# schematic.net
KiCad netlist of a schematic drawn in EAGLE
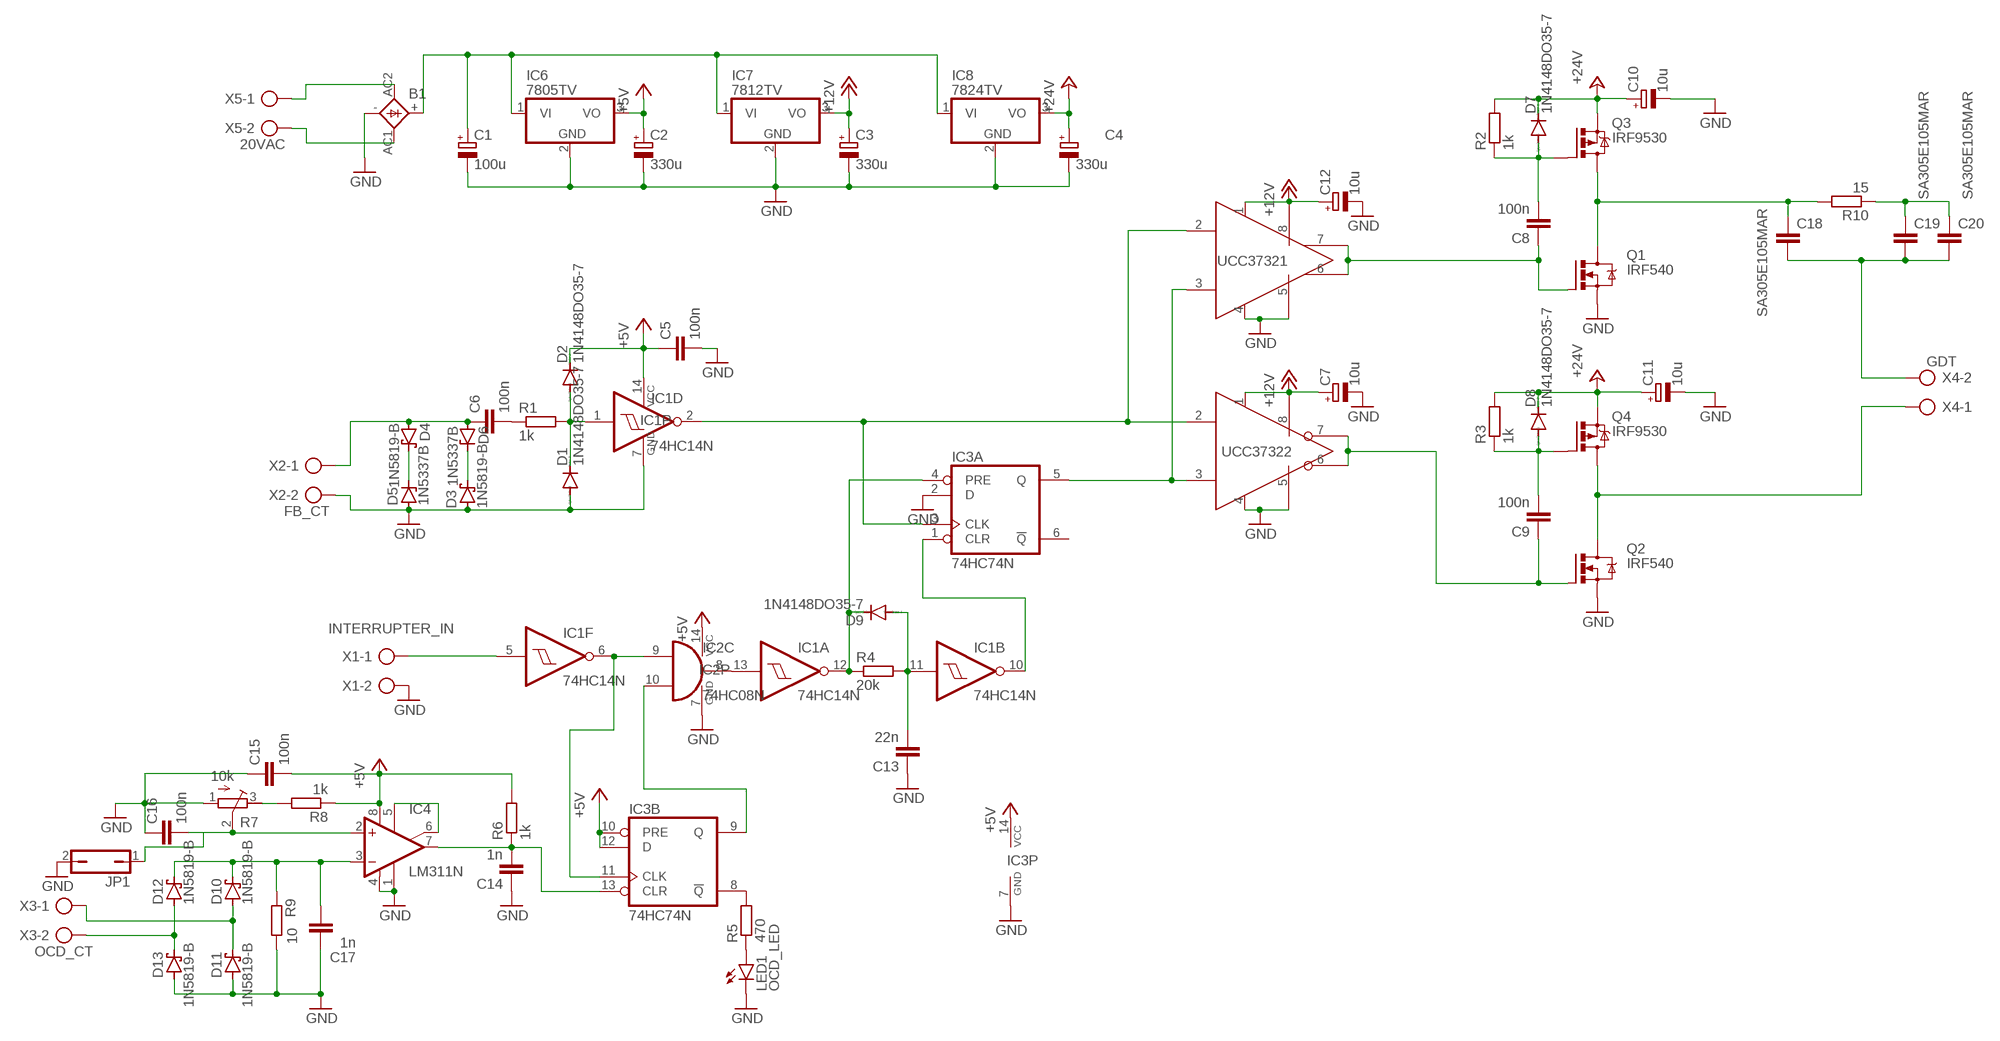
[diagram p0: schematic, sheet 1]

(export (version "E")
  (design (tool "Eeschema 10.0.6"))
  (components
    (comp (ref "B1")
      (value "KBL")
      (footprint "eagle-import:KBL")
      (libsource (lib "eagle-import") (part "KBL"))
    )
    (comp (ref "C1")
      (value "100u")
      (footprint "eagle-import:E3,5-10")
      (libsource (lib "eagle-import") (part "CPOL-EUE3.5-10"))
    )
    (comp (ref "C2")
      (value "330u")
      (footprint "eagle-import:E3,5-10")
      (libsource (lib "eagle-import") (part "CPOL-EUE3.5-10"))
    )
    (comp (ref "C3")
      (value "330u")
      (footprint "eagle-import:E3,5-10")
      (libsource (lib "eagle-import") (part "CPOL-EUE3.5-10"))
    )
    (comp (ref "C4")
      (value "330u")
      (footprint "eagle-import:E3,5-10")
      (libsource (lib "eagle-import") (part "CPOL-EUE3.5-10"))
    )
    (comp (ref "C5")
      (value "100n")
      (footprint "eagle-import:C050-030X075")
      (libsource (lib "eagle-import") (part "C-EU050-030X075"))
    )
    (comp (ref "C6")
      (value "100n")
      (footprint "eagle-import:C050-030X075")
      (libsource (lib "eagle-import") (part "C-EU050-030X075"))
    )
    (comp (ref "C7")
      (value "10u")
      (footprint "eagle-import:E2,5-6")
      (libsource (lib "eagle-import") (part "CPOL-EUE2.5-6"))
    )
    (comp (ref "C8")
      (value "100n")
      (footprint "eagle-import:C050-030X075")
      (libsource (lib "eagle-import") (part "C-EU050-030X075"))
    )
    (comp (ref "C9")
      (value "100n")
      (footprint "eagle-import:C050-030X075")
      (libsource (lib "eagle-import") (part "C-EU050-030X075"))
    )
    (comp (ref "C10")
      (value "10u")
      (footprint "eagle-import:E2,5-6")
      (libsource (lib "eagle-import") (part "CPOL-EUE2.5-6"))
    )
    (comp (ref "C11")
      (value "10u")
      (footprint "eagle-import:E2,5-6")
      (libsource (lib "eagle-import") (part "CPOL-EUE2.5-6"))
    )
    (comp (ref "C12")
      (value "10u")
      (footprint "eagle-import:E2,5-6")
      (libsource (lib "eagle-import") (part "CPOL-EUE2.5-6"))
    )
    (comp (ref "C13")
      (value "22n")
      (footprint "eagle-import:C050-030X075")
      (libsource (lib "eagle-import") (part "C-EU050-030X075"))
    )
    (comp (ref "C14")
      (value "1n")
      (footprint "eagle-import:C050-030X075")
      (libsource (lib "eagle-import") (part "C-EU050-030X075"))
    )
    (comp (ref "C15")
      (value "100n")
      (footprint "eagle-import:C050-030X075")
      (libsource (lib "eagle-import") (part "C-EU050-030X075"))
    )
    (comp (ref "C16")
      (value "100n")
      (footprint "eagle-import:C050-030X075")
      (libsource (lib "eagle-import") (part "C-EU050-030X075"))
    )
    (comp (ref "C17")
      (value "1n")
      (footprint "eagle-import:C050-030X075")
      (libsource (lib "eagle-import") (part "C-EU050-030X075"))
    )
    (comp (ref "C18")
      (value "SA305E105MAR")
      (footprint "eagle-import:C050-025X075")
      (libsource (lib "eagle-import") (part "resistor_348_C-EU050-025X075"))
    )
    (comp (ref "C19")
      (value "SA305E105MAR")
      (footprint "eagle-import:C050-025X075")
      (libsource (lib "eagle-import") (part "resistor_348_C-EU050-025X075"))
    )
    (comp (ref "C20")
      (value "SA305E105MAR")
      (footprint "eagle-import:C050-025X075")
      (libsource (lib "eagle-import") (part "resistor_348_C-EU050-025X075"))
    )
    (comp (ref "D1")
      (value "1N4148DO35-7")
      (footprint "eagle-import:DO35-7")
      (libsource (lib "eagle-import") (part "1N4148DO35-7"))
    )
    (comp (ref "D2")
      (value "1N4148DO35-7")
      (footprint "eagle-import:DO35-7")
      (libsource (lib "eagle-import") (part "1N4148DO35-7"))
    )
    (comp (ref "D3")
      (value "1N5819-B")
      (footprint "eagle-import:DO41-7.6")
      (libsource (lib "eagle-import") (part "1N5819-B"))
    )
    (comp (ref "D4")
      (value "1N5819-B")
      (footprint "eagle-import:DO41-7.6")
      (libsource (lib "eagle-import") (part "1N5819-B"))
    )
    (comp (ref "D5")
      (value "1N5337B")
      (footprint "eagle-import:DO41Z10")
      (libsource (lib "eagle-import") (part "ZENER-DIODEDO41Z10"))
    )
    (comp (ref "D6")
      (value "1N5337B")
      (footprint "eagle-import:DO41Z10")
      (libsource (lib "eagle-import") (part "ZENER-DIODEDO41Z10"))
    )
    (comp (ref "D7")
      (value "1N4148DO35-7")
      (footprint "eagle-import:DO35-7")
      (libsource (lib "eagle-import") (part "1N4148DO35-7"))
    )
    (comp (ref "D8")
      (value "1N4148DO35-7")
      (footprint "eagle-import:DO35-7")
      (libsource (lib "eagle-import") (part "1N4148DO35-7"))
    )
    (comp (ref "D9")
      (value "1N4148DO35-7")
      (footprint "eagle-import:DO35-7")
      (libsource (lib "eagle-import") (part "1N4148DO35-7"))
    )
    (comp (ref "D10")
      (value "1N5819-B")
      (footprint "eagle-import:DO41-7.6")
      (libsource (lib "eagle-import") (part "1N5819-B"))
    )
    (comp (ref "D11")
      (value "1N5819-B")
      (footprint "eagle-import:DO41-7.6")
      (libsource (lib "eagle-import") (part "1N5819-B"))
    )
    (comp (ref "D12")
      (value "1N5819-B")
      (footprint "eagle-import:DO41-7.6")
      (libsource (lib "eagle-import") (part "1N5819-B"))
    )
    (comp (ref "D13")
      (value "1N5819-B")
      (footprint "eagle-import:DO41-7.6")
      (libsource (lib "eagle-import") (part "1N5819-B"))
    )
    (comp (ref "IC1")
      (value "74HC14N")
      (footprint "eagle-import:DIL14")
      (libsource (lib "eagle-import") (part "7414NHC"))
    )
    (comp (ref "IC2")
      (value "74HC08N")
      (footprint "eagle-import:DIL14")
      (libsource (lib "eagle-import") (part "7408NHC"))
    )
    (comp (ref "IC3")
      (value "74HC74N")
      (footprint "eagle-import:DIL14")
      (libsource (lib "eagle-import") (part "7474NHC"))
    )
    (comp (ref "IC4")
      (value "LM311N")
      (footprint "eagle-import:DIL08")
      (libsource (lib "eagle-import") (part "LM311N"))
    )
    (comp (ref "IC5")
      (value "UCC37321DIL8")
      (footprint "eagle-import:DIL08")
      (fields (field (name "MF") "Texas Instruments") (field (name "MP") "UCC37321"))
      (libsource (lib "eagle-import") (part "UCC37321DIL8"))
    )
    (comp (ref "IC6")
      (value "7805TV")
      (footprint "eagle-import:TO220V")
      (libsource (lib "eagle-import") (part "78TV05"))
    )
    (comp (ref "IC7")
      (value "7812TV")
      (footprint "eagle-import:TO220V")
      (libsource (lib "eagle-import") (part "78TV12"))
    )
    (comp (ref "IC8")
      (value "7824TV")
      (footprint "eagle-import:TO220V")
      (libsource (lib "eagle-import") (part "78TV24"))
    )
    (comp (ref "IC9")
      (value "UCC37322DIL8")
      (footprint "eagle-import:DIL08")
      (fields (field (name "MF") "Texas Instruments") (field (name "MP") "UCC37322"))
      (libsource (lib "eagle-import") (part "UCC37322DIL8"))
    )
    (comp (ref "JP1")
      (value "JP1Q")
      (footprint "eagle-import:JP1")
      (libsource (lib "eagle-import") (part "JP1Q"))
    )
    (comp (ref "LED1")
      (value "OCD_LED")
      (footprint "eagle-import:LED3MM")
      (libsource (lib "eagle-import") (part "LED3MM"))
    )
    (comp (ref "Q1")
      (value "IRF540")
      (footprint "eagle-import:TO220BV")
      (libsource (lib "eagle-import") (part "IRF540"))
    )
    (comp (ref "Q2")
      (value "IRF540")
      (footprint "eagle-import:TO220BV")
      (libsource (lib "eagle-import") (part "IRF540"))
    )
    (comp (ref "Q3")
      (value "IRF9530")
      (footprint "eagle-import:TO220BV")
      (libsource (lib "eagle-import") (part "IRF9530"))
    )
    (comp (ref "Q4")
      (value "IRF9530")
      (footprint "eagle-import:TO220BV")
      (libsource (lib "eagle-import") (part "IRF9530"))
    )
    (comp (ref "R1")
      (value "1k")
      (footprint "eagle-import:0204_7")
      (libsource (lib "eagle-import") (part "R-EU_0204/7"))
    )
    (comp (ref "R2")
      (value "1k")
      (footprint "eagle-import:0204_7")
      (libsource (lib "eagle-import") (part "R-EU_0204/7"))
    )
    (comp (ref "R3")
      (value "1k")
      (footprint "eagle-import:0204_7")
      (libsource (lib "eagle-import") (part "R-EU_0204/7"))
    )
    (comp (ref "R4")
      (value "20k")
      (footprint "eagle-import:0204_7")
      (libsource (lib "eagle-import") (part "R-EU_0204/7"))
    )
    (comp (ref "R5")
      (value "470")
      (footprint "eagle-import:0204_7")
      (libsource (lib "eagle-import") (part "R-EU_0204/7"))
    )
    (comp (ref "R6")
      (value "1k")
      (footprint "eagle-import:0204_7")
      (libsource (lib "eagle-import") (part "R-EU_0204/7"))
    )
    (comp (ref "R7")
      (value "10k")
      (footprint "eagle-import:RTRIM64X")
      (libsource (lib "eagle-import") (part "R-TRIMM64X"))
    )
    (comp (ref "R8")
      (value "1k")
      (footprint "eagle-import:0204_7")
      (libsource (lib "eagle-import") (part "R-EU_0204/7"))
    )
    (comp (ref "R9")
      (value "10")
      (footprint "eagle-import:0411_15")
      (libsource (lib "eagle-import") (part "R-EU_0411/15"))
    )
    (comp (ref "R10")
      (value "15")
      (footprint "eagle-import:0204_7")
      (libsource (lib "eagle-import") (part "R-EU_0204/7"))
    )
    (comp (ref "X1")
      (value "INTERRUPTER_IN")
      (footprint "eagle-import:AK300_2")
      (libsource (lib "eagle-import") (part "AK300/2"))
    )
    (comp (ref "X2")
      (value "FB_CT")
      (footprint "eagle-import:AK300_2")
      (libsource (lib "eagle-import") (part "AK300/2"))
    )
    (comp (ref "X3")
      (value "OCD_CT")
      (footprint "eagle-import:AK300_2")
      (libsource (lib "eagle-import") (part "AK300/2"))
    )
    (comp (ref "X4")
      (value "GDT")
      (footprint "eagle-import:AK300_2")
      (libsource (lib "eagle-import") (part "AK300/2"))
    )
    (comp (ref "X5")
      (value "20VAC")
      (footprint "eagle-import:AK300_2")
      (libsource (lib "eagle-import") (part "AK300/2"))
    )
  )
  (nets
    (net (code "1") (name "+5V") (class "Default")
      (node (ref "C15") (pin "2") (pinfunction "2_2") (pintype "passive"))
      (node (ref "C2") (pin "+") (pinfunction "+_+") (pintype "passive"))
      (node (ref "C5") (pin "1") (pinfunction "1_1") (pintype "passive"))
      (node (ref "D2") (pin "C") (pinfunction "C_C") (pintype "passive"))
      (node (ref "IC1") (pin "14") (pinfunction "VCC_14") (pintype "power_in"))
      (node (ref "IC2") (pin "14") (pinfunction "VCC_14") (pintype "power_in"))
      (node (ref "IC3") (pin "10") (pinfunction "PRE_10") (pintype "input"))
      (node (ref "IC3") (pin "12") (pinfunction "D_12") (pintype "input"))
      (node (ref "IC3") (pin "14") (pinfunction "VCC_14") (pintype "power_in"))
      (node (ref "IC4") (pin "8") (pinfunction "V+_8") (pintype "power_in"))
      (node (ref "IC6") (pin "3") (pinfunction "VO_3") (pintype "passive"))
      (node (ref "R6") (pin "2") (pinfunction "2_2") (pintype "passive"))
      (node (ref "R8") (pin "1") (pinfunction "1_1") (pintype "passive"))
    )
    (net (code "2") (name "+12V") (class "Default")
      (node (ref "C12") (pin "+") (pinfunction "+_+") (pintype "passive"))
      (node (ref "C3") (pin "+") (pinfunction "+_+") (pintype "passive"))
      (node (ref "C7") (pin "+") (pinfunction "+_+") (pintype "passive"))
      (node (ref "IC5") (pin "1") (pinfunction "1_VDD_1") (pintype "power_in"))
      (node (ref "IC5") (pin "8") (pinfunction "8_VDD_8") (pintype "power_in"))
      (node (ref "IC7") (pin "3") (pinfunction "VO_3") (pintype "passive"))
      (node (ref "IC9") (pin "1") (pinfunction "1_VDD_1") (pintype "power_in"))
      (node (ref "IC9") (pin "8") (pinfunction "8_VDD_8") (pintype "power_in"))
    )
    (net (code "3") (name "+24V") (class "Default")
      (node (ref "C10") (pin "+") (pinfunction "+_+") (pintype "passive"))
      (node (ref "C11") (pin "+") (pinfunction "+_+") (pintype "passive"))
      (node (ref "C4") (pin "+") (pinfunction "+_+") (pintype "passive"))
      (node (ref "D7") (pin "C") (pinfunction "C_C") (pintype "passive"))
      (node (ref "D8") (pin "C") (pinfunction "C_C") (pintype "passive"))
      (node (ref "IC8") (pin "3") (pinfunction "VO_3") (pintype "passive"))
      (node (ref "Q3") (pin "S") (pinfunction "S_S") (pintype "passive"))
      (node (ref "Q4") (pin "S") (pinfunction "S_S") (pintype "passive"))
      (node (ref "R2") (pin "2") (pinfunction "2_2") (pintype "passive"))
      (node (ref "R3") (pin "2") (pinfunction "2_2") (pintype "passive"))
    )
    (net (code "4") (name "GND") (class "Default")
      (node (ref "B1") (pin "-") (pinfunction "-_-") (pintype "passive"))
      (node (ref "C1") (pin "-") (pinfunction "-_-") (pintype "passive"))
      (node (ref "C10") (pin "-") (pinfunction "-_-") (pintype "passive"))
      (node (ref "C11") (pin "-") (pinfunction "-_-") (pintype "passive"))
      (node (ref "C12") (pin "-") (pinfunction "-_-") (pintype "passive"))
      (node (ref "C13") (pin "1") (pinfunction "1_1") (pintype "passive"))
      (node (ref "C14") (pin "1") (pinfunction "1_1") (pintype "passive"))
      (node (ref "C15") (pin "1") (pinfunction "1_1") (pintype "passive"))
      (node (ref "C16") (pin "1") (pinfunction "1_1") (pintype "passive"))
      (node (ref "C17") (pin "1") (pinfunction "1_1") (pintype "passive"))
      (node (ref "C2") (pin "-") (pinfunction "-_-") (pintype "passive"))
      (node (ref "C3") (pin "-") (pinfunction "-_-") (pintype "passive"))
      (node (ref "C4") (pin "-") (pinfunction "-_-") (pintype "passive"))
      (node (ref "C5") (pin "2") (pinfunction "2_2") (pintype "passive"))
      (node (ref "C7") (pin "-") (pinfunction "-_-") (pintype "passive"))
      (node (ref "D1") (pin "A") (pinfunction "A_A") (pintype "passive"))
      (node (ref "D11") (pin "A") (pinfunction "A_A") (pintype "passive"))
      (node (ref "D13") (pin "A") (pinfunction "A_A") (pintype "passive"))
      (node (ref "D3") (pin "A") (pinfunction "A_A") (pintype "passive"))
      (node (ref "D5") (pin "A") (pinfunction "A_A") (pintype "passive"))
      (node (ref "IC1") (pin "7") (pinfunction "GND_7") (pintype "power_in"))
      (node (ref "IC2") (pin "7") (pinfunction "GND_7") (pintype "power_in"))
      (node (ref "IC3") (pin "2") (pinfunction "D_2") (pintype "input"))
      (node (ref "IC3") (pin "7") (pinfunction "GND_7") (pintype "power_in"))
      (node (ref "IC4") (pin "1") (pinfunction "GND_1") (pintype "passive"))
      (node (ref "IC4") (pin "4") (pinfunction "V-_4") (pintype "power_in"))
      (node (ref "IC5") (pin "4") (pinfunction "4_AGND_4") (pintype "power_in"))
      (node (ref "IC5") (pin "5") (pinfunction "5_PGND_5") (pintype "power_in"))
      (node (ref "IC6") (pin "2") (pinfunction "GND_2") (pintype "passive"))
      (node (ref "IC7") (pin "2") (pinfunction "GND_2") (pintype "passive"))
      (node (ref "IC8") (pin "2") (pinfunction "GND_2") (pintype "passive"))
      (node (ref "IC9") (pin "4") (pinfunction "4_AGND_4") (pintype "power_in"))
      (node (ref "IC9") (pin "5") (pinfunction "5_PGND_5") (pintype "power_in"))
      (node (ref "JP1") (pin "2") (pinfunction "2_2") (pintype "passive"))
      (node (ref "LED1") (pin "K") (pinfunction "C_K") (pintype "passive"))
      (node (ref "Q1") (pin "S") (pinfunction "S_S") (pintype "passive"))
      (node (ref "Q2") (pin "S") (pinfunction "S_S") (pintype "passive"))
      (node (ref "R7") (pin "1") (pinfunction "A_1") (pintype "passive"))
      (node (ref "R9") (pin "2") (pinfunction "2_2") (pintype "passive"))
      (node (ref "X1") (pin "2") (pinfunction "KL_2") (pintype "passive"))
      (node (ref "X2") (pin "2") (pinfunction "KL_2") (pintype "passive"))
    )
    (net (code "5") (name "Net-(B1-AC1)") (class "Default")
      (node (ref "B1") (pin "AC2") (pinfunction "AC1_AC2") (pintype "passive"))
      (node (ref "X5") (pin "1") (pinfunction "KL_1") (pintype "passive"))
    )
    (net (code "6") (name "Net-(B1-AC2)") (class "Default")
      (node (ref "B1") (pin "AC1") (pinfunction "AC2_AC1") (pintype "passive"))
      (node (ref "X5") (pin "2") (pinfunction "KL_2") (pintype "passive"))
    )
    (net (code "7") (name "Net-(C6-Pad2)") (class "Default")
      (node (ref "C6") (pin "2") (pinfunction "2_2") (pintype "passive"))
      (node (ref "R1") (pin "1") (pinfunction "1_1") (pintype "passive"))
    )
    (net (code "8") (name "Net-(C8-Pad2)") (class "Default")
      (node (ref "C8") (pin "2") (pinfunction "2_2") (pintype "passive"))
      (node (ref "D7") (pin "A") (pinfunction "A_A") (pintype "passive"))
      (node (ref "Q3") (pin "G") (pinfunction "G_G") (pintype "passive"))
      (node (ref "R2") (pin "1") (pinfunction "1_1") (pintype "passive"))
    )
    (net (code "9") (name "Net-(C9-Pad2)") (class "Default")
      (node (ref "C9") (pin "2") (pinfunction "2_2") (pintype "passive"))
      (node (ref "D8") (pin "A") (pinfunction "A_A") (pintype "passive"))
      (node (ref "Q4") (pin "G") (pinfunction "G_G") (pintype "passive"))
      (node (ref "R3") (pin "1") (pinfunction "1_1") (pintype "passive"))
    )
    (net (code "10") (name "Net-(C18-Pad1)") (class "Default")
      (node (ref "C18") (pin "1") (pinfunction "1_1") (pintype "passive"))
      (node (ref "Q1") (pin "D") (pinfunction "D_D") (pintype "passive"))
      (node (ref "Q3") (pin "D") (pinfunction "D_D") (pintype "passive"))
      (node (ref "R10") (pin "2") (pinfunction "2_2") (pintype "passive"))
    )
    (net (code "11") (name "Net-(C19-Pad1)") (class "Default")
      (node (ref "C19") (pin "1") (pinfunction "1_1") (pintype "passive"))
      (node (ref "C20") (pin "1") (pinfunction "1_1") (pintype "passive"))
      (node (ref "R10") (pin "1") (pinfunction "1_1") (pintype "passive"))
    )
    (net (code "12") (name "Net-(D3-PadC)") (class "Default")
      (node (ref "D3") (pin "C") (pinfunction "C_C") (pintype "passive"))
      (node (ref "D6") (pin "C") (pinfunction "C_C") (pintype "passive"))
    )
    (net (code "13") (name "Net-(D4-PadC)") (class "Default")
      (node (ref "D4") (pin "C") (pinfunction "C_C") (pintype "passive"))
      (node (ref "D5") (pin "C") (pinfunction "C_C") (pintype "passive"))
    )
    (net (code "14") (name "Net-(IC1A-I)") (class "Default")
      (node (ref "IC1") (pin "13") (pinfunction "I_13") (pintype "input"))
      (node (ref "IC2") (pin "8") (pinfunction "O_8") (pintype "output"))
    )
    (net (code "15") (name "Net-(IC1A-O)") (class "Default")
      (node (ref "D9") (pin "C") (pinfunction "C_C") (pintype "passive"))
      (node (ref "IC1") (pin "12") (pinfunction "O_12") (pintype "output"))
      (node (ref "IC3") (pin "4") (pinfunction "PRE_4") (pintype "input"))
      (node (ref "R4") (pin "1") (pinfunction "1_1") (pintype "passive"))
    )
    (net (code "16") (name "Net-(IC1B-I)") (class "Default")
      (node (ref "C13") (pin "2") (pinfunction "2_2") (pintype "passive"))
      (node (ref "D9") (pin "A") (pinfunction "A_A") (pintype "passive"))
      (node (ref "IC1") (pin "11") (pinfunction "I_11") (pintype "input"))
      (node (ref "R4") (pin "2") (pinfunction "2_2") (pintype "passive"))
    )
    (net (code "17") (name "Net-(IC1B-O)") (class "Default")
      (node (ref "IC1") (pin "10") (pinfunction "O_10") (pintype "output"))
      (node (ref "IC3") (pin "1") (pinfunction "CLR_1") (pintype "input"))
    )
    (net (code "18") (name "Net-(IC1D-I)") (class "Default")
      (node (ref "D1") (pin "C") (pinfunction "C_C") (pintype "passive"))
      (node (ref "D2") (pin "A") (pinfunction "A_A") (pintype "passive"))
      (node (ref "IC1") (pin "1") (pinfunction "I_1") (pintype "input"))
      (node (ref "R1") (pin "2") (pinfunction "2_2") (pintype "passive"))
    )
    (net (code "19") (name "Net-(IC1D-O)") (class "Default")
      (node (ref "IC1") (pin "2") (pinfunction "O_2") (pintype "output"))
      (node (ref "IC3") (pin "3") (pinfunction "CLK_3") (pintype "input"))
      (node (ref "IC5") (pin "2") (pinfunction "2_IN_2") (pintype "input"))
      (node (ref "IC9") (pin "2") (pinfunction "2_IN_2") (pintype "input"))
    )
    (net (code "20") (name "Net-(IC1F-I)") (class "Default")
      (node (ref "IC1") (pin "5") (pinfunction "I_5") (pintype "input"))
      (node (ref "X1") (pin "1") (pinfunction "KL_1") (pintype "passive"))
    )
    (net (code "21") (name "Net-(IC1F-O)") (class "Default")
      (node (ref "IC1") (pin "6") (pinfunction "O_6") (pintype "output"))
      (node (ref "IC2") (pin "9") (pinfunction "I0_9") (pintype "input"))
      (node (ref "IC3") (pin "11") (pinfunction "CLK_11") (pintype "input"))
    )
    (net (code "22") (name "Net-(IC2C-I1)") (class "Default")
      (node (ref "IC2") (pin "10") (pinfunction "I1_10") (pintype "input"))
      (node (ref "IC3") (pin "9") (pinfunction "Q_9") (pintype "output"))
    )
    (net (code "23") (name "Net-(IC3A-Q)") (class "Default")
      (node (ref "IC3") (pin "5") (pinfunction "Q_5") (pintype "output"))
      (node (ref "IC5") (pin "3") (pinfunction "3_ENBL_3") (pintype "input"))
      (node (ref "IC9") (pin "3") (pinfunction "3_ENBL_3") (pintype "input"))
    )
    (net (code "24") (name "Net-(IC3B-CLR)") (class "Default")
      (node (ref "C14") (pin "2") (pinfunction "2_2") (pintype "passive"))
      (node (ref "IC3") (pin "13") (pinfunction "CLR_13") (pintype "input"))
      (node (ref "IC4") (pin "7") (pinfunction "OUT_7") (pintype "output"))
      (node (ref "R6") (pin "1") (pinfunction "1_1") (pintype "passive"))
    )
    (net (code "25") (name "Net-(IC3B-~{Q})") (class "Default")
      (node (ref "IC3") (pin "8") (pinfunction "~{Q}_8") (pintype "output"))
      (node (ref "R5") (pin "2") (pinfunction "2_2") (pintype "passive"))
    )
    (net (code "26") (name "Net-(IC4-+IN)") (class "Default")
      (node (ref "C16") (pin "2") (pinfunction "2_2") (pintype "passive"))
      (node (ref "IC4") (pin "2") (pinfunction "+IN_2") (pintype "input"))
      (node (ref "JP1") (pin "1") (pinfunction "1_1") (pintype "passive"))
      (node (ref "R7") (pin "2") (pinfunction "S_2") (pintype "passive"))
    )
    (net (code "27") (name "Net-(IC4--IN)") (class "Default")
      (node (ref "C17") (pin "2") (pinfunction "2_2") (pintype "passive"))
      (node (ref "D10") (pin "C") (pinfunction "C_C") (pintype "passive"))
      (node (ref "D12") (pin "C") (pinfunction "C_C") (pintype "passive"))
      (node (ref "IC4") (pin "3") (pinfunction "-IN_3") (pintype "input"))
      (node (ref "R9") (pin "1") (pinfunction "1_1") (pintype "passive"))
    )
    (net (code "28") (name "Net-(IC4-ON)") (class "Default")
      (node (ref "IC4") (pin "5") (pinfunction "ON_5") (pintype "passive"))
      (node (ref "IC4") (pin "6") (pinfunction "ON/STR_6") (pintype "passive"))
    )
    (net (code "29") (name "Net-(IC5-6_OUT)") (class "Default")
      (node (ref "C8") (pin "1") (pinfunction "1_1") (pintype "passive"))
      (node (ref "IC5") (pin "6") (pinfunction "6_OUT_6") (pintype "output"))
      (node (ref "IC5") (pin "7") (pinfunction "7_OUT_7") (pintype "output"))
      (node (ref "Q1") (pin "G") (pinfunction "G_G") (pintype "passive"))
    )
    (net (code "30") (name "Net-(IC6-VI)") (class "Default")
      (node (ref "B1") (pin "+") (pinfunction "+_+") (pintype "passive"))
      (node (ref "C1") (pin "+") (pinfunction "+_+") (pintype "passive"))
      (node (ref "IC6") (pin "1") (pinfunction "VI_1") (pintype "input"))
      (node (ref "IC7") (pin "1") (pinfunction "VI_1") (pintype "input"))
      (node (ref "IC8") (pin "1") (pinfunction "VI_1") (pintype "input"))
    )
    (net (code "31") (name "Net-(IC9-6_OUT)") (class "Default")
      (node (ref "C9") (pin "1") (pinfunction "1_1") (pintype "passive"))
      (node (ref "IC9") (pin "6") (pinfunction "6_OUT_6") (pintype "output"))
      (node (ref "IC9") (pin "7") (pinfunction "7_OUT_7") (pintype "output"))
      (node (ref "Q2") (pin "G") (pinfunction "G_G") (pintype "passive"))
    )
    (net (code "32") (name "Net-(LED1-PadA)") (class "Default")
      (node (ref "LED1") (pin "A") (pinfunction "A_A") (pintype "passive"))
      (node (ref "R5") (pin "1") (pinfunction "1_1") (pintype "passive"))
    )
    (net (code "33") (name "Net-(R7-E)") (class "Default")
      (node (ref "R7") (pin "3") (pinfunction "E_3") (pintype "passive"))
      (node (ref "R8") (pin "2") (pinfunction "2_2") (pintype "passive"))
    )
    (net (code "34") (name "Net-(X2A-KL)") (class "Default")
      (node (ref "C6") (pin "1") (pinfunction "1_1") (pintype "passive"))
      (node (ref "D4") (pin "A") (pinfunction "A_A") (pintype "passive"))
      (node (ref "D6") (pin "A") (pinfunction "A_A") (pintype "passive"))
      (node (ref "X2") (pin "1") (pinfunction "KL_1") (pintype "passive"))
    )
    (net (code "35") (name "Net-(X3A-KL)") (class "Default")
      (node (ref "D10") (pin "A") (pinfunction "A_A") (pintype "passive"))
      (node (ref "D11") (pin "C") (pinfunction "C_C") (pintype "passive"))
      (node (ref "X3") (pin "1") (pinfunction "KL_1") (pintype "passive"))
    )
    (net (code "36") (name "Net-(X3B-KL)") (class "Default")
      (node (ref "D12") (pin "A") (pinfunction "A_A") (pintype "passive"))
      (node (ref "D13") (pin "C") (pinfunction "C_C") (pintype "passive"))
      (node (ref "X3") (pin "2") (pinfunction "KL_2") (pintype "passive"))
    )
    (net (code "37") (name "Net-(X4A-KL)") (class "Default")
      (node (ref "Q2") (pin "D") (pinfunction "D_D") (pintype "passive"))
      (node (ref "Q4") (pin "D") (pinfunction "D_D") (pintype "passive"))
      (node (ref "X4") (pin "1") (pinfunction "KL_1") (pintype "passive"))
    )
    (net (code "38") (name "Net-(X4B-KL)") (class "Default")
      (node (ref "C18") (pin "2") (pinfunction "2_2") (pintype "passive"))
      (node (ref "C19") (pin "2") (pinfunction "2_2") (pintype "passive"))
      (node (ref "C20") (pin "2") (pinfunction "2_2") (pintype "passive"))
      (node (ref "X4") (pin "2") (pinfunction "KL_2") (pintype "passive"))
    )
    (net (code "39") (name "unconnected-(IC3A-~{Q}-Pad6)") (class "Default")
      (node (ref "IC3") (pin "6") (pinfunction "~{Q}_6") (pintype "output"))
    )
  )
)
